# Power.net
KiCad netlist of a schematic drawn in Altium Designer
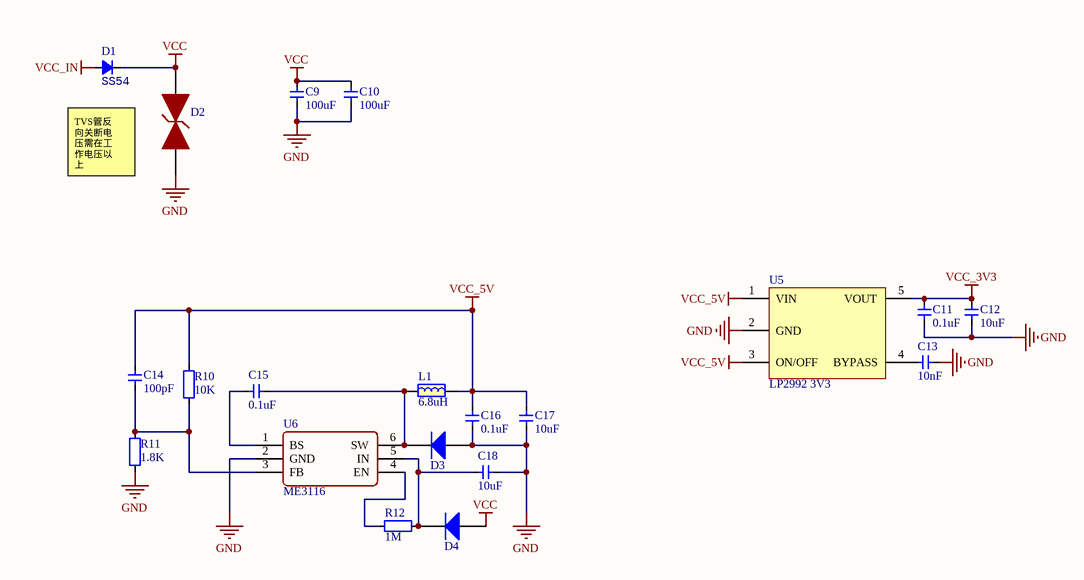
[diagram p0: Power.SchDoc]

(export (version "E")
  (design (tool "Eeschema 10.0.6"))
  (components
    (comp (ref "C9")
      (value "100uF")
      (footprint "1206-CAP")
      (description "Capacitor")
      (libsource (lib "MyPcbLib") (part "电容-1206"))
    )
    (comp (ref "C10")
      (value "100uF")
      (footprint "1206-CAP")
      (description "Capacitor")
      (libsource (lib "MyPcbLib") (part "电容-1206"))
    )
    (comp (ref "C11")
      (value "0.1uF")
      (footprint "CAP_0402")
      (description "Capacitor")
      (libsource (lib "MyPcbLib") (part "电容-0402"))
    )
    (comp (ref "C12")
      (value "10uF")
      (footprint "CAP_0402")
      (description "Capacitor")
      (libsource (lib "MyPcbLib") (part "电容-0402"))
    )
    (comp (ref "C13")
      (value "10nF")
      (footprint "CAP_0402")
      (description "Capacitor")
      (libsource (lib "MyPcbLib") (part "电容-0402"))
    )
    (comp (ref "C14")
      (value "100pF")
      (footprint "CAP_0402")
      (description "Capacitor")
      (libsource (lib "MyPcbLib") (part "电容-0402"))
    )
    (comp (ref "C15")
      (value "0.1uF")
      (footprint "CAP_0402")
      (description "Capacitor")
      (libsource (lib "MyPcbLib") (part "电容-0402"))
    )
    (comp (ref "C16")
      (value "0.1uF")
      (footprint "CAP_0402")
      (description "Capacitor")
      (libsource (lib "MyPcbLib") (part "电容-0402"))
    )
    (comp (ref "C17")
      (value "10uF")
      (footprint "CAP_0402")
      (description "Capacitor")
      (libsource (lib "MyPcbLib") (part "电容-0402"))
    )
    (comp (ref "C18")
      (value "10uF")
      (footprint "CAP_0402")
      (description "Capacitor")
      (libsource (lib "MyPcbLib") (part "电容-0402"))
    )
    (comp (ref "D1")
      (value "SS54")
      (footprint "DO-214AC")
      (description "Diode")
      (libsource (lib "KitSprout") (part "Diode_SMA"))
    )
    (comp (ref "D2")
      (value "SMBJ28CA")
      (footprint "SMBJ-CA_MFG")
      (libsource (lib "MyPcbLib") (part "SMBJ28CA"))
    )
    (comp (ref "D3")
      (value "二极管-5819W")
      (footprint "SOD-323")
      (description "40V")
      (libsource (lib "MyPcbLib") (part "二极管-5819W"))
    )
    (comp (ref "D4")
      (value "二极管-5819W")
      (footprint "SOD-323")
      (description "40V")
      (libsource (lib "MyPcbLib") (part "二极管-5819W"))
    )
    (comp (ref "L1") (value "6.8uH") (footprint "IND-201612") (libsource (lib "MyPcbLib") (part "电感-201612")))
    (comp (ref "R10")
      (value "10K")
      (footprint "RES_0402")
      (description "Resistor")
      (libsource (lib "") (part "电阻-0402_1"))
    )
    (comp (ref "R11")
      (value "1.8K")
      (footprint "RES_0402")
      (description "Resistor")
      (libsource (lib "") (part "电阻-0402_1"))
    )
    (comp (ref "R12")
      (value "1M")
      (footprint "RES_0402")
      (description "Resistor")
      (libsource (lib "MyPcbLib") (part "电阻-0402"))
    )
    (comp (ref "U5")
      (value "LP2992 3V3")
      (footprint "SOT23-5")
      (description "LDO")
      (libsource (lib "MyPcbLib") (part "LP2992"))
    )
    (comp (ref "U6")
      (value "ME3116")
      (footprint "SOT23-6")
      (description "DC-DC")
      (libsource (lib "MyPcbLib") (part "ME3116"))
    )
  )
  (nets
    (net (code "1") (name "GND") (class "Default")
      (node (ref "C10") (pin "1") (pinfunction "1_1") (pintype "passive"))
      (node (ref "C11") (pin "1") (pinfunction "1_1") (pintype "passive"))
      (node (ref "C12") (pin "1") (pinfunction "1_1") (pintype "passive"))
      (node (ref "C13") (pin "1") (pinfunction "1_1") (pintype "passive"))
      (node (ref "C16") (pin "1") (pinfunction "1_1") (pintype "passive"))
      (node (ref "C17") (pin "1") (pinfunction "1_1") (pintype "passive"))
      (node (ref "C18") (pin "1") (pinfunction "1_1") (pintype "passive"))
      (node (ref "C9") (pin "1") (pinfunction "1_1") (pintype "passive"))
      (node (ref "D2") (pin "1") (pinfunction "1_1") (pintype "passive"))
      (node (ref "D3") (pin "1") (pinfunction "A_1") (pintype "passive"))
      (node (ref "R11") (pin "1") (pinfunction "1_1") (pintype "passive"))
      (node (ref "U5") (pin "2") (pinfunction "GND_2") (pintype "passive"))
      (node (ref "U6") (pin "2") (pinfunction "GND_2") (pintype "passive"))
    )
    (net (code "2") (name "Net-(D3-K)") (class "Default")
      (node (ref "C15") (pin "1") (pinfunction "1_1") (pintype "passive"))
      (node (ref "D3") (pin "2") (pinfunction "K_2") (pintype "passive"))
      (node (ref "L1") (pin "1") (pintype "passive"))
      (node (ref "U6") (pin "6") (pinfunction "SW_6") (pintype "passive"))
    )
    (net (code "3") (name "Net-(D4-K)") (class "Default")
      (node (ref "C18") (pin "2") (pinfunction "2_2") (pintype "passive"))
      (node (ref "D4") (pin "2") (pinfunction "K_2") (pintype "passive"))
      (node (ref "R12") (pin "1") (pinfunction "1_1") (pintype "passive"))
      (node (ref "U6") (pin "5") (pinfunction "IN_5") (pintype "passive"))
    )
    (net (code "4") (name "Net-(U5-BYPASS)") (class "Default")
      (node (ref "C13") (pin "2") (pinfunction "2_2") (pintype "passive"))
      (node (ref "U5") (pin "4") (pinfunction "BYPASS_4") (pintype "passive"))
    )
    (net (code "5") (name "Net-(U6-BS)") (class "Default")
      (node (ref "C15") (pin "2") (pinfunction "2_2") (pintype "passive"))
      (node (ref "U6") (pin "1") (pinfunction "BS_1") (pintype "passive"))
    )
    (net (code "6") (name "Net-(U6-EN)") (class "Default")
      (node (ref "R12") (pin "2") (pinfunction "2_2") (pintype "passive"))
      (node (ref "U6") (pin "4") (pinfunction "EN_4") (pintype "passive"))
    )
    (net (code "7") (name "Net-(U6-FB)") (class "Default")
      (node (ref "C14") (pin "2") (pinfunction "2_2") (pintype "passive"))
      (node (ref "R10") (pin "1") (pinfunction "1_1") (pintype "passive"))
      (node (ref "R11") (pin "2") (pinfunction "2_2") (pintype "passive"))
      (node (ref "U6") (pin "3") (pinfunction "FB_3") (pintype "passive"))
    )
    (net (code "8") (name "VCC") (class "Default")
      (node (ref "C10") (pin "2") (pinfunction "2_2") (pintype "passive"))
      (node (ref "C9") (pin "2") (pinfunction "2_2") (pintype "passive"))
      (node (ref "D1") (pin "2") (pinfunction "K_2") (pintype "passive"))
      (node (ref "D2") (pin "2") (pinfunction "2_2") (pintype "passive"))
      (node (ref "D4") (pin "1") (pinfunction "A_1") (pintype "passive"))
    )
    (net (code "9") (name "VCC_3V3") (class "Default")
      (node (ref "C11") (pin "2") (pinfunction "2_2") (pintype "passive"))
      (node (ref "C12") (pin "2") (pinfunction "2_2") (pintype "passive"))
      (node (ref "U5") (pin "5") (pinfunction "VOUT_5") (pintype "passive"))
    )
    (net (code "10") (name "VCC_5V") (class "Default")
      (node (ref "C14") (pin "1") (pinfunction "1_1") (pintype "passive"))
      (node (ref "C16") (pin "2") (pinfunction "2_2") (pintype "passive"))
      (node (ref "C17") (pin "2") (pinfunction "2_2") (pintype "passive"))
      (node (ref "L1") (pin "2") (pinfunction "2_2") (pintype "passive"))
      (node (ref "R10") (pin "2") (pinfunction "2_2") (pintype "passive"))
      (node (ref "U5") (pin "1") (pinfunction "VIN_1") (pintype "passive"))
      (node (ref "U5") (pin "3") (pinfunction "ON/OFF_3") (pintype "passive"))
    )
    (net (code "11") (name "VCC_IN") (class "Default")
      (node (ref "D1") (pin "1") (pinfunction "A_1") (pintype "passive"))
    )
  )
)
